# Font__light_connect.net
KiCad netlist of a schematic drawn in EAGLE
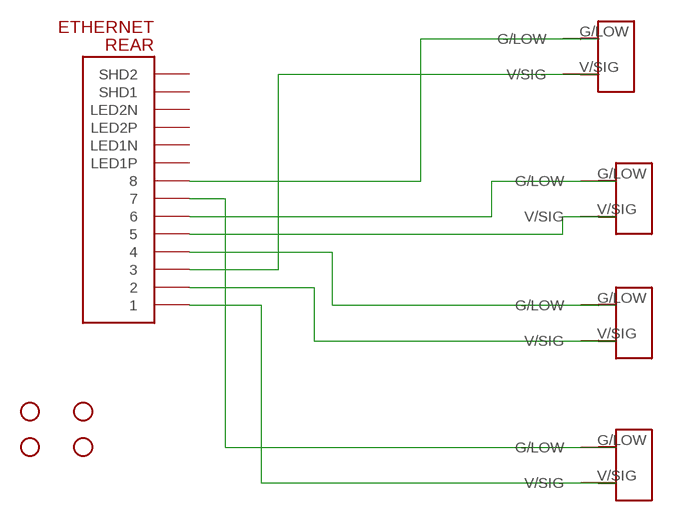
[diagram p0: schematic, sheet 1]

(export (version "E")
  (design (tool "Eeschema 10.0.6"))
  (components
    (comp (ref "H1")
      (value "STAND-OFF")
      (footprint "eagle-import:STAND-OFF")
      (libsource (lib "eagle-import") (part "STAND-OFF"))
    )
    (comp (ref "H2")
      (value "STAND-OFF")
      (footprint "eagle-import:STAND-OFF")
      (libsource (lib "eagle-import") (part "STAND-OFF"))
    )
    (comp (ref "H3")
      (value "STAND-OFF")
      (footprint "eagle-import:STAND-OFF")
      (libsource (lib "eagle-import") (part "STAND-OFF"))
    )
    (comp (ref "H4")
      (value "STAND-OFF")
      (footprint "eagle-import:STAND-OFF")
      (libsource (lib "eagle-import") (part "STAND-OFF"))
    )
    (comp (ref "L_DRIVE")
      (value "2_PIN_TECONNECTOR")
      (footprint "eagle-import:2_PIN_CONNECT")
      (libsource (lib "eagle-import") (part "2_PIN_TECONNECTOR"))
    )
    (comp (ref "L_SIG")
      (value "2_PIN_TECONNECTOR")
      (footprint "eagle-import:2_PIN_CONNECT")
      (libsource (lib "eagle-import") (part "2_PIN_TECONNECTOR"))
    )
    (comp (ref "REAR")
      (value "ETHERNET")
      (footprint "eagle-import:A122645-ND")
      (libsource (lib "eagle-import") (part "ETHERNET"))
    )
    (comp (ref "R_SIG")
      (value "2_PIN_TECONNECTOR")
      (footprint "eagle-import:2_PIN_CONNECT")
      (libsource (lib "eagle-import") (part "2_PIN_TECONNECTOR"))
    )
    (comp (ref "T_DRIVE")
      (value "2_PIN_TECONNECTOR")
      (footprint "eagle-import:2_PIN_CONNECT")
      (libsource (lib "eagle-import") (part "2_PIN_TECONNECTOR"))
    )
  )
  (nets
    (net (code "1") (name "Net-(REAR-1)") (class "Default")
      (node (ref "L_DRIVE") (pin "V/SIG") (pinfunction "V/SIG_V/SIG") (pintype "bidirectional"))
      (node (ref "REAR") (pin "P$1") (pinfunction "1_P$1") (pintype "bidirectional"))
    )
    (net (code "2") (name "Net-(REAR-2)") (class "Default")
      (node (ref "L_SIG") (pin "V/SIG") (pinfunction "V/SIG_V/SIG") (pintype "bidirectional"))
      (node (ref "REAR") (pin "P$2") (pinfunction "2_P$2") (pintype "bidirectional"))
    )
    (net (code "3") (name "Net-(REAR-3)") (class "Default")
      (node (ref "REAR") (pin "P$3") (pinfunction "3_P$3") (pintype "bidirectional"))
      (node (ref "T_DRIVE") (pin "V/SIG") (pinfunction "V/SIG_V/SIG") (pintype "bidirectional"))
    )
    (net (code "4") (name "Net-(REAR-4)") (class "Default")
      (node (ref "L_SIG") (pin "G/LOW") (pinfunction "G/LOW_G/LOW") (pintype "bidirectional"))
      (node (ref "REAR") (pin "P$4") (pinfunction "4_P$4") (pintype "bidirectional"))
    )
    (net (code "5") (name "Net-(REAR-5)") (class "Default")
      (node (ref "REAR") (pin "P$5") (pinfunction "5_P$5") (pintype "bidirectional"))
      (node (ref "R_SIG") (pin "V/SIG") (pinfunction "V/SIG_V/SIG") (pintype "bidirectional"))
    )
    (net (code "6") (name "Net-(REAR-6)") (class "Default")
      (node (ref "REAR") (pin "P$6") (pinfunction "6_P$6") (pintype "bidirectional"))
      (node (ref "R_SIG") (pin "G/LOW") (pinfunction "G/LOW_G/LOW") (pintype "bidirectional"))
    )
    (net (code "7") (name "Net-(REAR-7)") (class "Default")
      (node (ref "L_DRIVE") (pin "G/LOW") (pinfunction "G/LOW_G/LOW") (pintype "bidirectional"))
      (node (ref "REAR") (pin "P$7") (pinfunction "7_P$7") (pintype "bidirectional"))
    )
    (net (code "8") (name "Net-(REAR-8)") (class "Default")
      (node (ref "REAR") (pin "P$8") (pinfunction "8_P$8") (pintype "bidirectional"))
      (node (ref "T_DRIVE") (pin "G/LOW") (pinfunction "G/LOW_G/LOW") (pintype "bidirectional"))
    )
    (net (code "9") (name "unconnected-(REAR-LED1N-PadP$9)") (class "Default")
      (node (ref "REAR") (pin "P$9") (pinfunction "LED1N_P$9") (pintype "bidirectional"))
    )
    (net (code "10") (name "unconnected-(REAR-LED1P-PadP$10)") (class "Default")
      (node (ref "REAR") (pin "P$10") (pinfunction "LED1P_P$10") (pintype "bidirectional"))
    )
    (net (code "11") (name "unconnected-(REAR-LED2N-PadP$11)") (class "Default")
      (node (ref "REAR") (pin "P$11") (pinfunction "LED2N_P$11") (pintype "bidirectional"))
    )
    (net (code "12") (name "unconnected-(REAR-LED2P-PadP$12)") (class "Default")
      (node (ref "REAR") (pin "P$12") (pinfunction "LED2P_P$12") (pintype "bidirectional"))
    )
    (net (code "13") (name "unconnected-(REAR-SHD1-PadP$13)") (class "Default")
      (node (ref "REAR") (pin "P$13") (pinfunction "SHD1_P$13") (pintype "bidirectional"))
    )
    (net (code "14") (name "unconnected-(REAR-SHD2-PadP$14)") (class "Default")
      (node (ref "REAR") (pin "P$14") (pinfunction "SHD2_P$14") (pintype "bidirectional"))
    )
  )
)
